# Camera_Schematics.net
KiCad netlist of a schematic drawn in Altium Designer
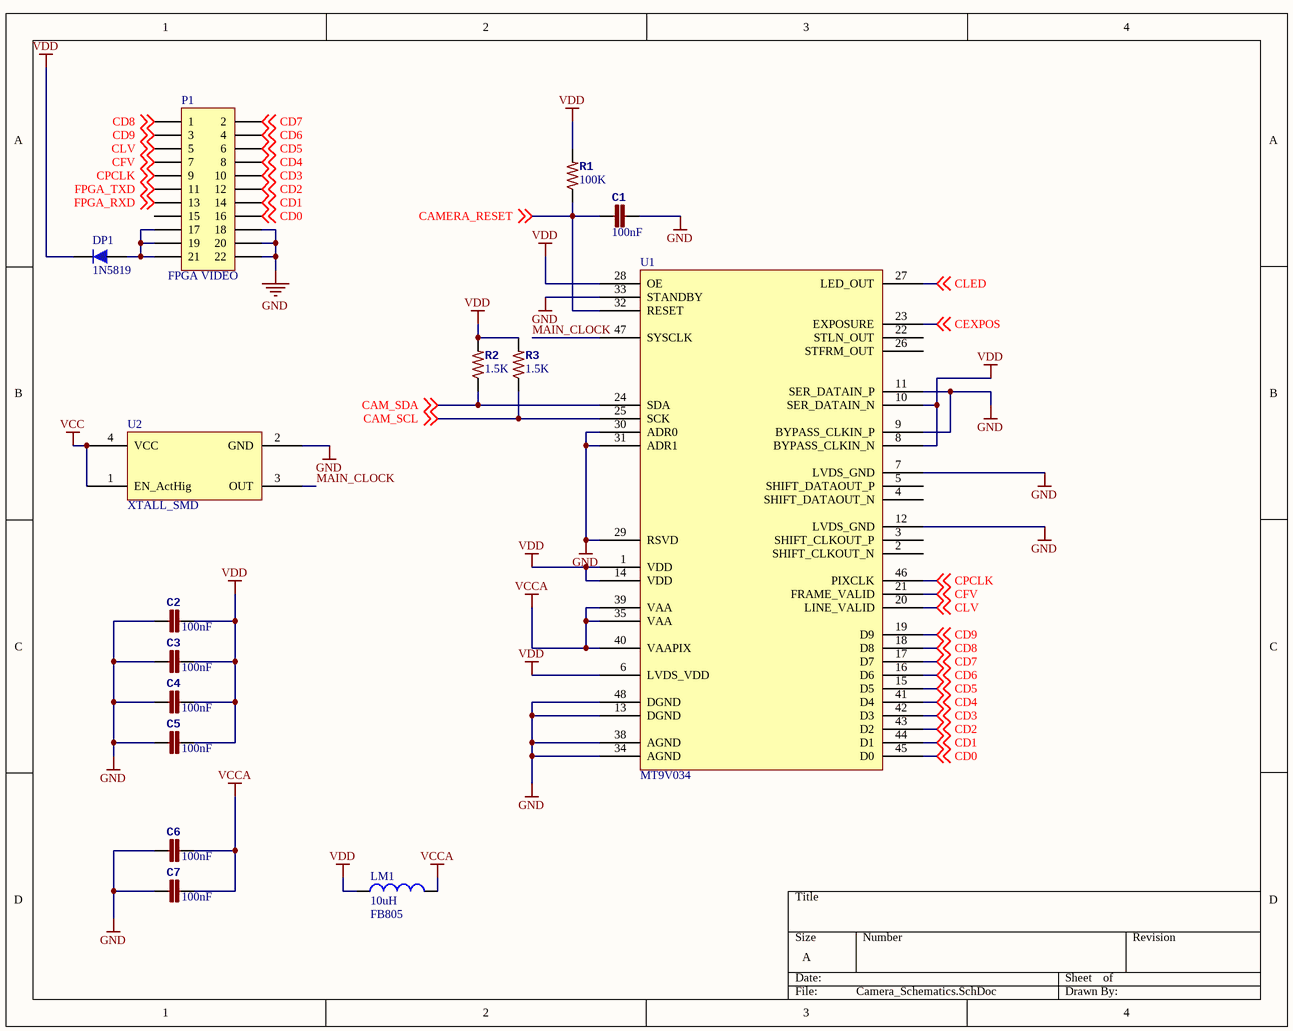
[diagram p0: Camera_Schematics.SchDoc]

(export (version "E")
  (design (tool "Eeschema 10.0.6"))
  (components
    (comp (ref "C1")
      (value "100nF")
      (footprint "_0805")
      (fields (field (name "Comment") "Cap"))
      (libsource (lib "Passives_Integrated_Library") (part "Cap_1"))
    )
    (comp (ref "C2")
      (value "100nF")
      (footprint "_0805")
      (fields (field (name "Comment") "Cap"))
      (libsource (lib "Passives_Integrated_Library") (part "Cap_1"))
    )
    (comp (ref "C3")
      (value "100nF")
      (footprint "_0805")
      (fields (field (name "Comment") "Cap"))
      (libsource (lib "Passives_Integrated_Library") (part "Cap_1"))
    )
    (comp (ref "C4")
      (value "100nF")
      (footprint "_0805")
      (fields (field (name "Comment") "Cap"))
      (libsource (lib "Passives_Integrated_Library") (part "Cap_1"))
    )
    (comp (ref "C5")
      (value "100nF")
      (footprint "_0805")
      (fields (field (name "Comment") "Cap"))
      (libsource (lib "Passives_Integrated_Library") (part "Cap_1"))
    )
    (comp (ref "C6")
      (value "100nF")
      (footprint "_0805")
      (fields (field (name "Comment") "Cap"))
      (libsource (lib "Passives_Integrated_Library") (part "Cap_1"))
    )
    (comp (ref "C7")
      (value "100nF")
      (footprint "_0805")
      (fields (field (name "Comment") "Cap"))
      (libsource (lib "Passives_Integrated_Library") (part "Cap_1"))
    )
    (comp (ref "DP1")
      (value "1N5819")
      (footprint "430X270D")
      (description "Schottkey Rectifiers")
      (fields (field (name "DESIGNER") "Abbas Basereh"))
      (libsource (lib "Diodes_Integrated_Library") (part "1N5819"))
    )
    (comp (ref "LM1")
      (value "10uH")
      (footprint "0805L")
      (description "Inductor")
      (fields (field (name "ALTIUM_VALUE") "FB805") (field (name "PUBLISHER") "Altium Limited"))
      (libsource (lib "Passives_Integrated_Library") (part "L SMA 0.25W"))
    )
    (comp (ref "P1")
      (value "FPGA VIDEO")
      (footprint "HDR2X11")
      (description "Header, 11-Pin, Dual row")
      (fields (field (name "PUBLISHER") "Altium Limited"))
      (libsource (lib "Miscellaneous Connectors") (part "Header 11X2"))
    )
    (comp (ref "R1")
      (value "100K")
      (footprint "_0603")
      (fields (field (name "Comment") "Resistor"))
      (libsource (lib "Passives_Integrated_Library") (part "Resistor"))
    )
    (comp (ref "R2")
      (value "1.5K")
      (footprint "_0603")
      (fields (field (name "Comment") "Resistor"))
      (libsource (lib "Passives_Integrated_Library") (part "Resistor"))
    )
    (comp (ref "R3")
      (value "1.5K")
      (footprint "_0603")
      (fields (field (name "Comment") "Resistor"))
      (libsource (lib "Passives_Integrated_Library") (part "Resistor"))
    )
    (comp (ref "U1")
      (value "MT9V034")
      (footprint "MT9V034")
      (libsource (lib "Sensors_Integrated_Library") (part "MT9V034"))
    )
    (comp (ref "U2")
      (value "XTALL_SMD")
      (footprint "XTAL_SMD")
      (libsource (lib "Passives_Integrated_Library") (part "XTAL_SMD"))
    )
  )
  (nets
    (net (code "1") (name "/MAIN_CLOCK") (class "Default")
      (node (ref "U1") (pin "47") (pinfunction "SYSCLK_47") (pintype "passive"))
      (node (ref "U2") (pin "3") (pinfunction "OUT_3") (pintype "passive"))
    )
    (net (code "2") (name "CAMERA_RESET") (class "Default")
      (node (ref "C1") (pin "1") (pinfunction "1_1") (pintype "passive"))
      (node (ref "R1") (pin "1") (pinfunction "1_1") (pintype "passive"))
      (node (ref "U1") (pin "32") (pinfunction "RESET_32") (pintype "passive"))
    )
    (net (code "3") (name "CAM_SCL") (class "Default")
      (node (ref "R3") (pin "1") (pinfunction "1_1") (pintype "passive"))
      (node (ref "U1") (pin "25") (pinfunction "SCK_25") (pintype "passive"))
    )
    (net (code "4") (name "CAM_SDA") (class "Default")
      (node (ref "R2") (pin "1") (pinfunction "1_1") (pintype "passive"))
      (node (ref "U1") (pin "24") (pinfunction "SDA_24") (pintype "passive"))
    )
    (net (code "5") (name "CD0") (class "Default")
      (node (ref "P1") (pin "16") (pinfunction "16_16") (pintype "passive"))
      (node (ref "U1") (pin "45") (pinfunction "D0_45") (pintype "passive"))
    )
    (net (code "6") (name "CD1") (class "Default")
      (node (ref "P1") (pin "14") (pinfunction "14_14") (pintype "passive"))
      (node (ref "U1") (pin "44") (pinfunction "D1_44") (pintype "passive"))
    )
    (net (code "7") (name "CD2") (class "Default")
      (node (ref "P1") (pin "12") (pinfunction "12_12") (pintype "passive"))
      (node (ref "U1") (pin "43") (pinfunction "D2_43") (pintype "passive"))
    )
    (net (code "8") (name "CD3") (class "Default")
      (node (ref "P1") (pin "10") (pinfunction "10_10") (pintype "passive"))
      (node (ref "U1") (pin "42") (pinfunction "D3_42") (pintype "passive"))
    )
    (net (code "9") (name "CD4") (class "Default")
      (node (ref "P1") (pin "8") (pinfunction "8_8") (pintype "passive"))
      (node (ref "U1") (pin "41") (pinfunction "D4_41") (pintype "passive"))
    )
    (net (code "10") (name "CD5") (class "Default")
      (node (ref "P1") (pin "6") (pinfunction "6_6") (pintype "passive"))
      (node (ref "U1") (pin "15") (pinfunction "D5_15") (pintype "passive"))
    )
    (net (code "11") (name "CD6") (class "Default")
      (node (ref "P1") (pin "4") (pinfunction "4_4") (pintype "passive"))
      (node (ref "U1") (pin "16") (pinfunction "D6_16") (pintype "passive"))
    )
    (net (code "12") (name "CD7") (class "Default")
      (node (ref "P1") (pin "2") (pinfunction "2_2") (pintype "passive"))
      (node (ref "U1") (pin "17") (pinfunction "D7_17") (pintype "passive"))
    )
    (net (code "13") (name "CD8") (class "Default")
      (node (ref "P1") (pin "1") (pinfunction "1_1") (pintype "passive"))
      (node (ref "U1") (pin "18") (pinfunction "D8_18") (pintype "passive"))
    )
    (net (code "14") (name "CD9") (class "Default")
      (node (ref "P1") (pin "3") (pinfunction "3_3") (pintype "passive"))
      (node (ref "U1") (pin "19") (pinfunction "D9_19") (pintype "passive"))
    )
    (net (code "15") (name "CEXPOS") (class "Default")
      (node (ref "U1") (pin "23") (pinfunction "EXPOSURE_23") (pintype "passive"))
    )
    (net (code "16") (name "CFV") (class "Default")
      (node (ref "P1") (pin "7") (pinfunction "7_7") (pintype "passive"))
      (node (ref "U1") (pin "21") (pinfunction "FRAME_VALID_21") (pintype "passive"))
    )
    (net (code "17") (name "CLED") (class "Default")
      (node (ref "U1") (pin "27") (pinfunction "LED_OUT_27") (pintype "passive"))
    )
    (net (code "18") (name "CLV") (class "Default")
      (node (ref "P1") (pin "5") (pinfunction "5_5") (pintype "passive"))
      (node (ref "U1") (pin "20") (pinfunction "LINE_VALID_20") (pintype "passive"))
    )
    (net (code "19") (name "CPCLK") (class "Default")
      (node (ref "P1") (pin "9") (pinfunction "9_9") (pintype "passive"))
      (node (ref "U1") (pin "46") (pinfunction "PIXCLK_46") (pintype "passive"))
    )
    (net (code "20") (name "FPGA_RXD") (class "Default")
      (node (ref "P1") (pin "13") (pinfunction "13_13") (pintype "passive"))
    )
    (net (code "21") (name "FPGA_TXD") (class "Default")
      (node (ref "P1") (pin "11") (pinfunction "11_11") (pintype "passive"))
    )
    (net (code "22") (name "GND") (class "Default")
      (node (ref "C1") (pin "2") (pinfunction "2_2") (pintype "passive"))
      (node (ref "C2") (pin "1") (pinfunction "1_1") (pintype "passive"))
      (node (ref "C3") (pin "1") (pinfunction "1_1") (pintype "passive"))
      (node (ref "C4") (pin "1") (pinfunction "1_1") (pintype "passive"))
      (node (ref "C5") (pin "1") (pinfunction "1_1") (pintype "passive"))
      (node (ref "C6") (pin "1") (pinfunction "1_1") (pintype "passive"))
      (node (ref "C7") (pin "1") (pinfunction "1_1") (pintype "passive"))
      (node (ref "P1") (pin "18") (pinfunction "18_18") (pintype "passive"))
      (node (ref "P1") (pin "20") (pinfunction "20_20") (pintype "passive"))
      (node (ref "P1") (pin "22") (pinfunction "22_22") (pintype "passive"))
      (node (ref "U1") (pin "11") (pinfunction "SER_DATAIN_P_11") (pintype "passive"))
      (node (ref "U1") (pin "12") (pinfunction "LVDS_GND_12") (pintype "passive"))
      (node (ref "U1") (pin "13") (pinfunction "DGND_13") (pintype "passive"))
      (node (ref "U1") (pin "29") (pinfunction "RSVD_29") (pintype "passive"))
      (node (ref "U1") (pin "30") (pinfunction "ADR0_30") (pintype "passive"))
      (node (ref "U1") (pin "31") (pinfunction "ADR1_31") (pintype "passive"))
      (node (ref "U1") (pin "33") (pinfunction "STANDBY_33") (pintype "passive"))
      (node (ref "U1") (pin "34") (pinfunction "AGND_34") (pintype "passive"))
      (node (ref "U1") (pin "38") (pinfunction "AGND_38") (pintype "passive"))
      (node (ref "U1") (pin "48") (pinfunction "DGND_48") (pintype "passive"))
      (node (ref "U1") (pin "7") (pinfunction "LVDS_GND_7") (pintype "passive"))
      (node (ref "U1") (pin "9") (pinfunction "BYPASS_CLKIN_P_9") (pintype "passive"))
      (node (ref "U2") (pin "2") (pinfunction "GND_2") (pintype "passive"))
    )
    (net (code "23") (name "Net-(DP1-Pad1)") (class "Default")
      (node (ref "DP1") (pin "1") (pintype "passive"))
      (node (ref "P1") (pin "17") (pinfunction "17_17") (pintype "passive"))
      (node (ref "P1") (pin "19") (pinfunction "19_19") (pintype "passive"))
      (node (ref "P1") (pin "21") (pinfunction "21_21") (pintype "passive"))
    )
    (net (code "24") (name "VCC") (class "Default")
      (node (ref "U2") (pin "1") (pinfunction "EN_ActHig_1") (pintype "passive"))
      (node (ref "U2") (pin "4") (pinfunction "VCC_4") (pintype "passive"))
    )
    (net (code "25") (name "VCCA") (class "Default")
      (node (ref "C6") (pin "2") (pinfunction "2_2") (pintype "passive"))
      (node (ref "C7") (pin "2") (pinfunction "2_2") (pintype "passive"))
      (node (ref "LM1") (pin "2") (pinfunction "2_2") (pintype "passive"))
      (node (ref "U1") (pin "35") (pinfunction "VAA_35") (pintype "passive"))
      (node (ref "U1") (pin "39") (pinfunction "VAA_39") (pintype "passive"))
      (node (ref "U1") (pin "40") (pinfunction "VAAPIX_40") (pintype "passive"))
    )
    (net (code "26") (name "VDD") (class "Default")
      (node (ref "C2") (pin "2") (pinfunction "2_2") (pintype "passive"))
      (node (ref "C3") (pin "2") (pinfunction "2_2") (pintype "passive"))
      (node (ref "C4") (pin "2") (pinfunction "2_2") (pintype "passive"))
      (node (ref "C5") (pin "2") (pinfunction "2_2") (pintype "passive"))
      (node (ref "DP1") (pin "2") (pintype "passive"))
      (node (ref "LM1") (pin "1") (pinfunction "1_1") (pintype "passive"))
      (node (ref "R1") (pin "2") (pinfunction "2_2") (pintype "passive"))
      (node (ref "R2") (pin "2") (pinfunction "2_2") (pintype "passive"))
      (node (ref "R3") (pin "2") (pinfunction "2_2") (pintype "passive"))
      (node (ref "U1") (pin "1") (pinfunction "VDD_1") (pintype "passive"))
      (node (ref "U1") (pin "10") (pinfunction "SER_DATAIN_N_10") (pintype "passive"))
      (node (ref "U1") (pin "14") (pinfunction "VDD_14") (pintype "passive"))
      (node (ref "U1") (pin "28") (pinfunction "OE_28") (pintype "passive"))
      (node (ref "U1") (pin "6") (pinfunction "LVDS_VDD_6") (pintype "passive"))
      (node (ref "U1") (pin "8") (pinfunction "BYPASS_CLKIN_N_8") (pintype "passive"))
    )
    (net (code "27") (name "unconnected-(P1-Pad15)") (class "Default")
      (node (ref "P1") (pin "15") (pinfunction "15_15") (pintype "passive"))
    )
    (net (code "28") (name "unconnected-(U1-SHIFT_CLKOUT_N-Pad2)") (class "Default")
      (node (ref "U1") (pin "2") (pinfunction "SHIFT_CLKOUT_N_2") (pintype "passive"))
    )
    (net (code "29") (name "unconnected-(U1-SHIFT_CLKOUT_P-Pad3)") (class "Default")
      (node (ref "U1") (pin "3") (pinfunction "SHIFT_CLKOUT_P_3") (pintype "passive"))
    )
    (net (code "30") (name "unconnected-(U1-SHIFT_DATAOUT_N-Pad4)") (class "Default")
      (node (ref "U1") (pin "4") (pinfunction "SHIFT_DATAOUT_N_4") (pintype "passive"))
    )
    (net (code "31") (name "unconnected-(U1-SHIFT_DATAOUT_P-Pad5)") (class "Default")
      (node (ref "U1") (pin "5") (pinfunction "SHIFT_DATAOUT_P_5") (pintype "passive"))
    )
    (net (code "32") (name "unconnected-(U1-STFRM_OUT-Pad26)") (class "Default")
      (node (ref "U1") (pin "26") (pinfunction "STFRM_OUT_26") (pintype "passive"))
    )
    (net (code "33") (name "unconnected-(U1-STLN_OUT-Pad22)") (class "Default")
      (node (ref "U1") (pin "22") (pinfunction "STLN_OUT_22") (pintype "passive"))
    )
  )
)
